# 10_LPDDR_SDRAM2.net
KiCad netlist of a schematic drawn in Altium Designer
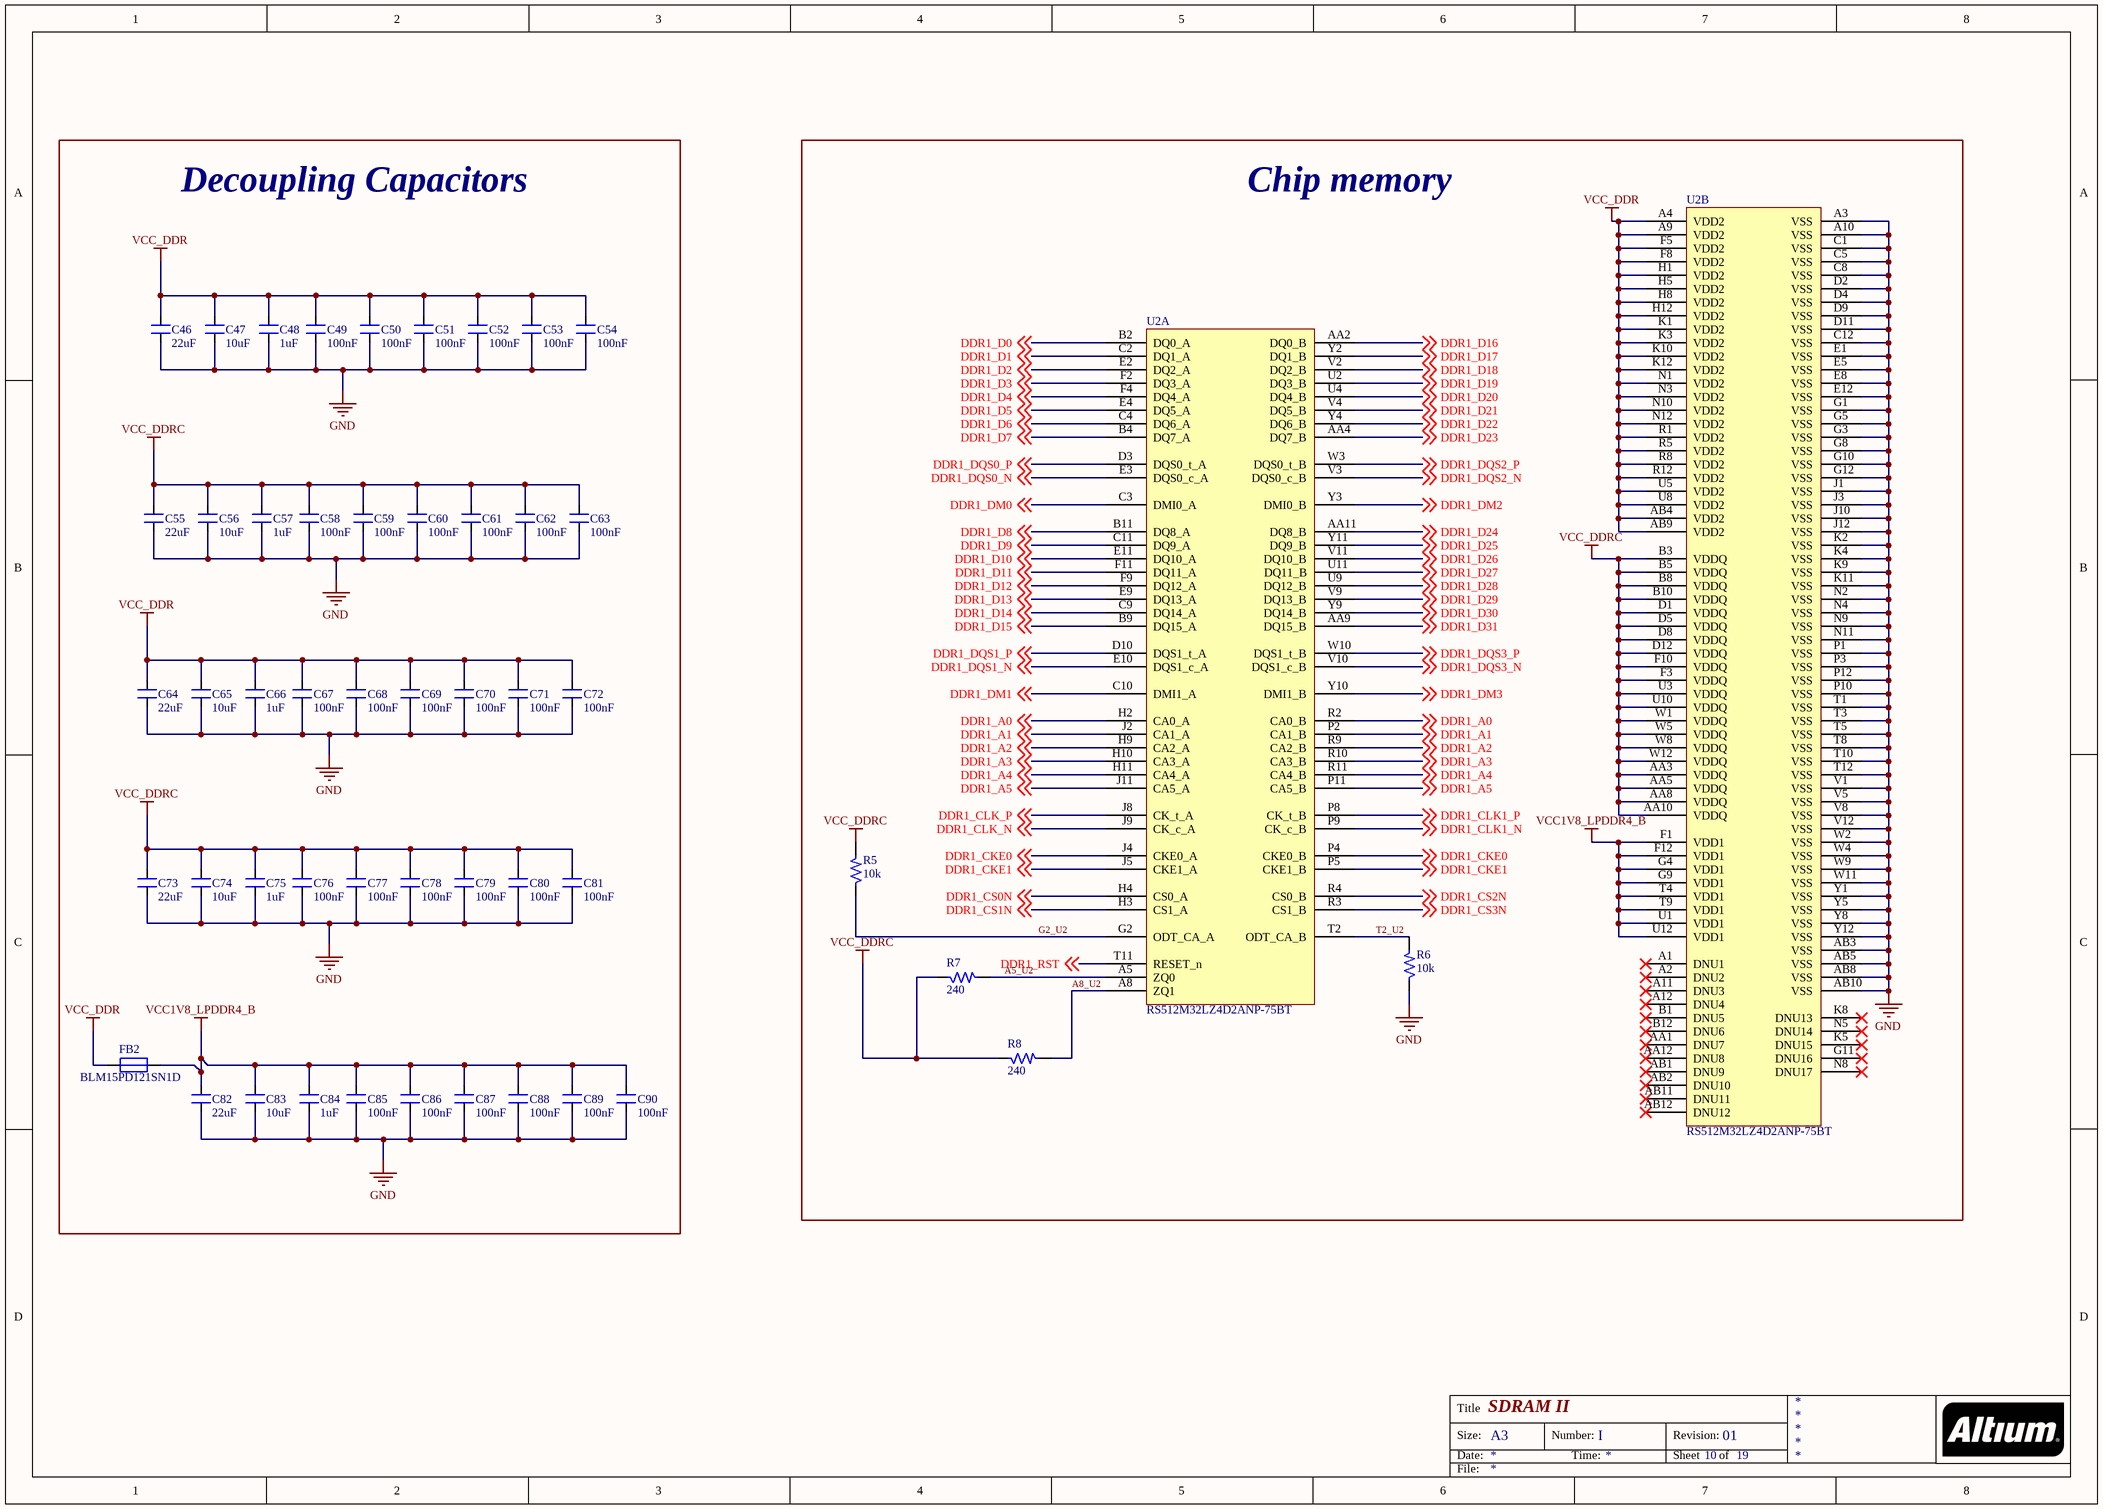
[diagram p0: [10] LPDDR_SDRAM2.SchDoc]

(export (version "E")
  (design (tool "Eeschema 10.0.6"))
  (components
    (comp (ref "C46")
      (value "22uF")
      (footprint "CAP_0402")
      (description "22µF ±20% 6.3V Ceramic Capacitor X5R 0402 (1005 Metric)")
      (fields
        (field (name "MANUFACTURER") "Murata Electronics")
        (field (name "MANUFACTURER PART NUMBER") "CL05A226MQ5N6J8")
      )
      (libsource (lib "EsteemPCB_SOM_Course_intlib") (part "CAP_22uF-6.3V-20%-0402"))
    )
    (comp (ref "C47")
      (value "10uF")
      (footprint "CAP_0402")
      (description "10µF ±20% 10V Ceramic Capacitor X5R 0402 (1005 Metric)")
      (fields
        (field (name "MANUFACTURER PART NUMBER") "CL05A106MP5NUNC")
        (field (name "MANUFACTURER") "Samsung Electro-Mechanics")
      )
      (libsource (lib "EsteemPCB_SOM_Course_intlib") (part "CAP_10uF-10V-20%-0402"))
    )
    (comp (ref "C48")
      (value "1uF")
      (footprint "CAP_0201")
      (description "1µF ±20% 16V Ceramic Capacitor X5R 0201 (0603 Metric)")
      (fields
        (field (name "MANUFACTURER") "Samsung Electro-Mechanics")
        (field (name "MANUFACTURER PART NUMBER") "CL03A105MO3NRNH")
      )
      (libsource (lib "EsteemPCB_SOM_Course_intlib") (part "CAP_1uF-16V-10%-0201"))
    )
    (comp (ref "C49")
      (value "100nF")
      (footprint "CAP_0201")
      (description "0.1µF ±10% 25V Ceramic Capacitor X5R 0201 (0603 Metric)")
      (fields
        (field (name "MANUFACTURER") "TDK Corporation")
        (field (name "MANUFACTURER PART NUMBER") "C0603X5R1E104K030BB")
      )
      (libsource (lib "EsteemPCB_SOM_Course_intlib") (part "CAP_100nF-25V-10%-0201"))
    )
    (comp (ref "C50")
      (value "100nF")
      (footprint "CAP_0201")
      (description "0.1µF ±10% 25V Ceramic Capacitor X5R 0201 (0603 Metric)")
      (fields
        (field (name "MANUFACTURER") "TDK Corporation")
        (field (name "MANUFACTURER PART NUMBER") "C0603X5R1E104K030BB")
      )
      (libsource (lib "EsteemPCB_SOM_Course_intlib") (part "CAP_100nF-25V-10%-0201"))
    )
    (comp (ref "C51")
      (value "100nF")
      (footprint "CAP_0201")
      (description "0.1µF ±10% 25V Ceramic Capacitor X5R 0201 (0603 Metric)")
      (fields
        (field (name "MANUFACTURER") "TDK Corporation")
        (field (name "MANUFACTURER PART NUMBER") "C0603X5R1E104K030BB")
      )
      (libsource (lib "EsteemPCB_SOM_Course_intlib") (part "CAP_100nF-25V-10%-0201"))
    )
    (comp (ref "C52")
      (value "100nF")
      (footprint "CAP_0201")
      (description "0.1µF ±10% 25V Ceramic Capacitor X5R 0201 (0603 Metric)")
      (fields
        (field (name "MANUFACTURER") "TDK Corporation")
        (field (name "MANUFACTURER PART NUMBER") "C0603X5R1E104K030BB")
      )
      (libsource (lib "EsteemPCB_SOM_Course_intlib") (part "CAP_100nF-25V-10%-0201"))
    )
    (comp (ref "C53")
      (value "100nF")
      (footprint "CAP_0201")
      (description "0.1µF ±10% 25V Ceramic Capacitor X5R 0201 (0603 Metric)")
      (fields
        (field (name "MANUFACTURER") "TDK Corporation")
        (field (name "MANUFACTURER PART NUMBER") "C0603X5R1E104K030BB")
      )
      (libsource (lib "EsteemPCB_SOM_Course_intlib") (part "CAP_100nF-25V-10%-0201"))
    )
    (comp (ref "C54")
      (value "100nF")
      (footprint "CAP_0201")
      (description "0.1µF ±10% 25V Ceramic Capacitor X5R 0201 (0603 Metric)")
      (fields
        (field (name "MANUFACTURER") "TDK Corporation")
        (field (name "MANUFACTURER PART NUMBER") "C0603X5R1E104K030BB")
      )
      (libsource (lib "EsteemPCB_SOM_Course_intlib") (part "CAP_100nF-25V-10%-0201"))
    )
    (comp (ref "C55")
      (value "22uF")
      (footprint "CAP_0402")
      (description "22µF ±20% 6.3V Ceramic Capacitor X5R 0402 (1005 Metric)")
      (fields
        (field (name "MANUFACTURER") "Murata Electronics")
        (field (name "MANUFACTURER PART NUMBER") "CL05A226MQ5N6J8")
      )
      (libsource (lib "EsteemPCB_SOM_Course_intlib") (part "CAP_22uF-6.3V-20%-0402"))
    )
    (comp (ref "C56")
      (value "10uF")
      (footprint "CAP_0402")
      (description "10µF ±20% 10V Ceramic Capacitor X5R 0402 (1005 Metric)")
      (fields
        (field (name "MANUFACTURER PART NUMBER") "CL05A106MP5NUNC")
        (field (name "MANUFACTURER") "Samsung Electro-Mechanics")
      )
      (libsource (lib "EsteemPCB_SOM_Course_intlib") (part "CAP_10uF-10V-20%-0402"))
    )
    (comp (ref "C57")
      (value "1uF")
      (footprint "CAP_0201")
      (description "1µF ±20% 16V Ceramic Capacitor X5R 0201 (0603 Metric)")
      (fields
        (field (name "MANUFACTURER") "Samsung Electro-Mechanics")
        (field (name "MANUFACTURER PART NUMBER") "CL03A105MO3NRNH")
      )
      (libsource (lib "EsteemPCB_SOM_Course_intlib") (part "CAP_1uF-16V-10%-0201"))
    )
    (comp (ref "C58")
      (value "100nF")
      (footprint "CAP_0201")
      (description "0.1µF ±10% 25V Ceramic Capacitor X5R 0201 (0603 Metric)")
      (fields
        (field (name "MANUFACTURER") "TDK Corporation")
        (field (name "MANUFACTURER PART NUMBER") "C0603X5R1E104K030BB")
      )
      (libsource (lib "EsteemPCB_SOM_Course_intlib") (part "CAP_100nF-25V-10%-0201"))
    )
    (comp (ref "C59")
      (value "100nF")
      (footprint "CAP_0201")
      (description "0.1µF ±10% 25V Ceramic Capacitor X5R 0201 (0603 Metric)")
      (fields
        (field (name "MANUFACTURER") "TDK Corporation")
        (field (name "MANUFACTURER PART NUMBER") "C0603X5R1E104K030BB")
      )
      (libsource (lib "EsteemPCB_SOM_Course_intlib") (part "CAP_100nF-25V-10%-0201"))
    )
    (comp (ref "C60")
      (value "100nF")
      (footprint "CAP_0201")
      (description "0.1µF ±10% 25V Ceramic Capacitor X5R 0201 (0603 Metric)")
      (fields
        (field (name "MANUFACTURER") "TDK Corporation")
        (field (name "MANUFACTURER PART NUMBER") "C0603X5R1E104K030BB")
      )
      (libsource (lib "EsteemPCB_SOM_Course_intlib") (part "CAP_100nF-25V-10%-0201"))
    )
    (comp (ref "C61")
      (value "100nF")
      (footprint "CAP_0201")
      (description "0.1µF ±10% 25V Ceramic Capacitor X5R 0201 (0603 Metric)")
      (fields
        (field (name "MANUFACTURER") "TDK Corporation")
        (field (name "MANUFACTURER PART NUMBER") "C0603X5R1E104K030BB")
      )
      (libsource (lib "EsteemPCB_SOM_Course_intlib") (part "CAP_100nF-25V-10%-0201"))
    )
    (comp (ref "C62")
      (value "100nF")
      (footprint "CAP_0201")
      (description "0.1µF ±10% 25V Ceramic Capacitor X5R 0201 (0603 Metric)")
      (fields
        (field (name "MANUFACTURER") "TDK Corporation")
        (field (name "MANUFACTURER PART NUMBER") "C0603X5R1E104K030BB")
      )
      (libsource (lib "EsteemPCB_SOM_Course_intlib") (part "CAP_100nF-25V-10%-0201"))
    )
    (comp (ref "C63")
      (value "100nF")
      (footprint "CAP_0201")
      (description "0.1µF ±10% 25V Ceramic Capacitor X5R 0201 (0603 Metric)")
      (fields
        (field (name "MANUFACTURER") "TDK Corporation")
        (field (name "MANUFACTURER PART NUMBER") "C0603X5R1E104K030BB")
      )
      (libsource (lib "EsteemPCB_SOM_Course_intlib") (part "CAP_100nF-25V-10%-0201"))
    )
    (comp (ref "C64")
      (value "22uF")
      (footprint "CAP_0402")
      (description "22µF ±20% 6.3V Ceramic Capacitor X5R 0402 (1005 Metric)")
      (fields
        (field (name "MANUFACTURER") "Murata Electronics")
        (field (name "MANUFACTURER PART NUMBER") "CL05A226MQ5N6J8")
      )
      (libsource (lib "EsteemPCB_SOM_Course_intlib") (part "CAP_22uF-6.3V-20%-0402"))
    )
    (comp (ref "C65")
      (value "10uF")
      (footprint "CAP_0402")
      (description "10µF ±20% 10V Ceramic Capacitor X5R 0402 (1005 Metric)")
      (fields
        (field (name "MANUFACTURER PART NUMBER") "CL05A106MP5NUNC")
        (field (name "MANUFACTURER") "Samsung Electro-Mechanics")
      )
      (libsource (lib "EsteemPCB_SOM_Course_intlib") (part "CAP_10uF-10V-20%-0402"))
    )
    (comp (ref "C66")
      (value "1uF")
      (footprint "CAP_0201")
      (description "1µF ±20% 16V Ceramic Capacitor X5R 0201 (0603 Metric)")
      (fields
        (field (name "MANUFACTURER") "Samsung Electro-Mechanics")
        (field (name "MANUFACTURER PART NUMBER") "CL03A105MO3NRNH")
      )
      (libsource (lib "EsteemPCB_SOM_Course_intlib") (part "CAP_1uF-16V-10%-0201"))
    )
    (comp (ref "C67")
      (value "100nF")
      (footprint "CAP_0201")
      (description "0.1µF ±10% 25V Ceramic Capacitor X5R 0201 (0603 Metric)")
      (fields
        (field (name "MANUFACTURER") "TDK Corporation")
        (field (name "MANUFACTURER PART NUMBER") "C0603X5R1E104K030BB")
      )
      (libsource (lib "EsteemPCB_SOM_Course_intlib") (part "CAP_100nF-25V-10%-0201"))
    )
    (comp (ref "C68")
      (value "100nF")
      (footprint "CAP_0201")
      (description "0.1µF ±10% 25V Ceramic Capacitor X5R 0201 (0603 Metric)")
      (fields
        (field (name "MANUFACTURER") "TDK Corporation")
        (field (name "MANUFACTURER PART NUMBER") "C0603X5R1E104K030BB")
      )
      (libsource (lib "EsteemPCB_SOM_Course_intlib") (part "CAP_100nF-25V-10%-0201"))
    )
    (comp (ref "C69")
      (value "100nF")
      (footprint "CAP_0201")
      (description "0.1µF ±10% 25V Ceramic Capacitor X5R 0201 (0603 Metric)")
      (fields
        (field (name "MANUFACTURER") "TDK Corporation")
        (field (name "MANUFACTURER PART NUMBER") "C0603X5R1E104K030BB")
      )
      (libsource (lib "EsteemPCB_SOM_Course_intlib") (part "CAP_100nF-25V-10%-0201"))
    )
    (comp (ref "C70")
      (value "100nF")
      (footprint "CAP_0201")
      (description "0.1µF ±10% 25V Ceramic Capacitor X5R 0201 (0603 Metric)")
      (fields
        (field (name "MANUFACTURER") "TDK Corporation")
        (field (name "MANUFACTURER PART NUMBER") "C0603X5R1E104K030BB")
      )
      (libsource (lib "EsteemPCB_SOM_Course_intlib") (part "CAP_100nF-25V-10%-0201"))
    )
    (comp (ref "C71")
      (value "100nF")
      (footprint "CAP_0201")
      (description "0.1µF ±10% 25V Ceramic Capacitor X5R 0201 (0603 Metric)")
      (fields
        (field (name "MANUFACTURER") "TDK Corporation")
        (field (name "MANUFACTURER PART NUMBER") "C0603X5R1E104K030BB")
      )
      (libsource (lib "EsteemPCB_SOM_Course_intlib") (part "CAP_100nF-25V-10%-0201"))
    )
    (comp (ref "C72")
      (value "100nF")
      (footprint "CAP_0201")
      (description "0.1µF ±10% 25V Ceramic Capacitor X5R 0201 (0603 Metric)")
      (fields
        (field (name "MANUFACTURER") "TDK Corporation")
        (field (name "MANUFACTURER PART NUMBER") "C0603X5R1E104K030BB")
      )
      (libsource (lib "EsteemPCB_SOM_Course_intlib") (part "CAP_100nF-25V-10%-0201"))
    )
    (comp (ref "C73")
      (value "22uF")
      (footprint "CAP_0402")
      (description "22µF ±20% 6.3V Ceramic Capacitor X5R 0402 (1005 Metric)")
      (fields
        (field (name "MANUFACTURER") "Murata Electronics")
        (field (name "MANUFACTURER PART NUMBER") "CL05A226MQ5N6J8")
      )
      (libsource (lib "EsteemPCB_SOM_Course_intlib") (part "CAP_22uF-6.3V-20%-0402"))
    )
    (comp (ref "C74")
      (value "10uF")
      (footprint "CAP_0402")
      (description "10µF ±20% 10V Ceramic Capacitor X5R 0402 (1005 Metric)")
      (fields
        (field (name "MANUFACTURER PART NUMBER") "CL05A106MP5NUNC")
        (field (name "MANUFACTURER") "Samsung Electro-Mechanics")
      )
      (libsource (lib "EsteemPCB_SOM_Course_intlib") (part "CAP_10uF-10V-20%-0402"))
    )
    (comp (ref "C75")
      (value "1uF")
      (footprint "CAP_0201")
      (description "1µF ±20% 16V Ceramic Capacitor X5R 0201 (0603 Metric)")
      (fields
        (field (name "MANUFACTURER") "Samsung Electro-Mechanics")
        (field (name "MANUFACTURER PART NUMBER") "CL03A105MO3NRNH")
      )
      (libsource (lib "EsteemPCB_SOM_Course_intlib") (part "CAP_1uF-16V-10%-0201"))
    )
    (comp (ref "C76")
      (value "100nF")
      (footprint "CAP_0201")
      (description "0.1µF ±10% 25V Ceramic Capacitor X5R 0201 (0603 Metric)")
      (fields
        (field (name "MANUFACTURER") "TDK Corporation")
        (field (name "MANUFACTURER PART NUMBER") "C0603X5R1E104K030BB")
      )
      (libsource (lib "EsteemPCB_SOM_Course_intlib") (part "CAP_100nF-25V-10%-0201"))
    )
    (comp (ref "C77")
      (value "100nF")
      (footprint "CAP_0201")
      (description "0.1µF ±10% 25V Ceramic Capacitor X5R 0201 (0603 Metric)")
      (fields
        (field (name "MANUFACTURER") "TDK Corporation")
        (field (name "MANUFACTURER PART NUMBER") "C0603X5R1E104K030BB")
      )
      (libsource (lib "EsteemPCB_SOM_Course_intlib") (part "CAP_100nF-25V-10%-0201"))
    )
    (comp (ref "C78")
      (value "100nF")
      (footprint "CAP_0201")
      (description "0.1µF ±10% 25V Ceramic Capacitor X5R 0201 (0603 Metric)")
      (fields
        (field (name "MANUFACTURER") "TDK Corporation")
        (field (name "MANUFACTURER PART NUMBER") "C0603X5R1E104K030BB")
      )
      (libsource (lib "EsteemPCB_SOM_Course_intlib") (part "CAP_100nF-25V-10%-0201"))
    )
    (comp (ref "C79")
      (value "100nF")
      (footprint "CAP_0201")
      (description "0.1µF ±10% 25V Ceramic Capacitor X5R 0201 (0603 Metric)")
      (fields
        (field (name "MANUFACTURER") "TDK Corporation")
        (field (name "MANUFACTURER PART NUMBER") "C0603X5R1E104K030BB")
      )
      (libsource (lib "EsteemPCB_SOM_Course_intlib") (part "CAP_100nF-25V-10%-0201"))
    )
    (comp (ref "C80")
      (value "100nF")
      (footprint "CAP_0201")
      (description "0.1µF ±10% 25V Ceramic Capacitor X5R 0201 (0603 Metric)")
      (fields
        (field (name "MANUFACTURER") "TDK Corporation")
        (field (name "MANUFACTURER PART NUMBER") "C0603X5R1E104K030BB")
      )
      (libsource (lib "EsteemPCB_SOM_Course_intlib") (part "CAP_100nF-25V-10%-0201"))
    )
    (comp (ref "C81")
      (value "100nF")
      (footprint "CAP_0201")
      (description "0.1µF ±10% 25V Ceramic Capacitor X5R 0201 (0603 Metric)")
      (fields
        (field (name "MANUFACTURER") "TDK Corporation")
        (field (name "MANUFACTURER PART NUMBER") "C0603X5R1E104K030BB")
      )
      (libsource (lib "EsteemPCB_SOM_Course_intlib") (part "CAP_100nF-25V-10%-0201"))
    )
    (comp (ref "C82")
      (value "22uF")
      (footprint "CAP_0402")
      (description "22µF ±20% 6.3V Ceramic Capacitor X5R 0402 (1005 Metric)")
      (fields
        (field (name "MANUFACTURER") "Murata Electronics")
        (field (name "MANUFACTURER PART NUMBER") "CL05A226MQ5N6J8")
      )
      (libsource (lib "EsteemPCB_SOM_Course_intlib") (part "CAP_22uF-6.3V-20%-0402"))
    )
    (comp (ref "C83")
      (value "10uF")
      (footprint "CAP_0402")
      (description "10µF ±20% 10V Ceramic Capacitor X5R 0402 (1005 Metric)")
      (fields
        (field (name "MANUFACTURER PART NUMBER") "CL05A106MP5NUNC")
        (field (name "MANUFACTURER") "Samsung Electro-Mechanics")
      )
      (libsource (lib "EsteemPCB_SOM_Course_intlib") (part "CAP_10uF-10V-20%-0402"))
    )
    (comp (ref "C84")
      (value "1uF")
      (footprint "CAP_0201")
      (description "1µF ±20% 16V Ceramic Capacitor X5R 0201 (0603 Metric)")
      (fields
        (field (name "MANUFACTURER") "Samsung Electro-Mechanics")
        (field (name "MANUFACTURER PART NUMBER") "CL03A105MO3NRNH")
      )
      (libsource (lib "EsteemPCB_SOM_Course_intlib") (part "CAP_1uF-16V-10%-0201"))
    )
    (comp (ref "C85")
      (value "100nF")
      (footprint "CAP_0201")
      (description "0.1µF ±10% 25V Ceramic Capacitor X5R 0201 (0603 Metric)")
      (fields
        (field (name "MANUFACTURER") "TDK Corporation")
        (field (name "MANUFACTURER PART NUMBER") "C0603X5R1E104K030BB")
      )
      (libsource (lib "EsteemPCB_SOM_Course_intlib") (part "CAP_100nF-25V-10%-0201"))
    )
    (comp (ref "C86")
      (value "100nF")
      (footprint "CAP_0201")
      (description "0.1µF ±10% 25V Ceramic Capacitor X5R 0201 (0603 Metric)")
      (fields
        (field (name "MANUFACTURER") "TDK Corporation")
        (field (name "MANUFACTURER PART NUMBER") "C0603X5R1E104K030BB")
      )
      (libsource (lib "EsteemPCB_SOM_Course_intlib") (part "CAP_100nF-25V-10%-0201"))
    )
    (comp (ref "C87")
      (value "100nF")
      (footprint "CAP_0201")
      (description "0.1µF ±10% 25V Ceramic Capacitor X5R 0201 (0603 Metric)")
      (fields
        (field (name "MANUFACTURER") "TDK Corporation")
        (field (name "MANUFACTURER PART NUMBER") "C0603X5R1E104K030BB")
      )
      (libsource (lib "EsteemPCB_SOM_Course_intlib") (part "CAP_100nF-25V-10%-0201"))
    )
    (comp (ref "C88")
      (value "100nF")
      (footprint "CAP_0201")
      (description "0.1µF ±10% 25V Ceramic Capacitor X5R 0201 (0603 Metric)")
      (fields
        (field (name "MANUFACTURER") "TDK Corporation")
        (field (name "MANUFACTURER PART NUMBER") "C0603X5R1E104K030BB")
      )
      (libsource (lib "EsteemPCB_SOM_Course_intlib") (part "CAP_100nF-25V-10%-0201"))
    )
    (comp (ref "C89")
      (value "100nF")
      (footprint "CAP_0201")
      (description "0.1µF ±10% 25V Ceramic Capacitor X5R 0201 (0603 Metric)")
      (fields
        (field (name "MANUFACTURER") "TDK Corporation")
        (field (name "MANUFACTURER PART NUMBER") "C0603X5R1E104K030BB")
      )
      (libsource (lib "EsteemPCB_SOM_Course_intlib") (part "CAP_100nF-25V-10%-0201"))
    )
    (comp (ref "C90")
      (value "100nF")
      (footprint "CAP_0201")
      (description "0.1µF ±10% 25V Ceramic Capacitor X5R 0201 (0603 Metric)")
      (fields
        (field (name "MANUFACTURER") "TDK Corporation")
        (field (name "MANUFACTURER PART NUMBER") "C0603X5R1E104K030BB")
      )
      (libsource (lib "EsteemPCB_SOM_Course_intlib") (part "CAP_100nF-25V-10%-0201"))
    )
    (comp (ref "FB2")
      (value "BLM15PD121SN1D")
      (footprint "RES_0402")
      (description "120 Ohms @ 100MHz 1 Power Line Ferrite Bead 0402 (1005 Metric) 1.3A 90mOhm")
      (fields (field (name "MANUFACTURER") "Murata Electronics"))
      (libsource (lib "EsteemPCB_SOM_Course_intlib") (part "FB_120R-1.3A-100Mhz-0402"))
    )
    (comp (ref "R5")
      (value "10k")
      (footprint "RES_0201")
      (description "0 Ohms Jumper 0.05W, 1/20W Chip Resistor 0201 (0603 Metric) Automotive AEC-Q200 Thick Film")
      (fields
        (field (name "MANUFACTURER") "Bourns Inc.")
        (field (name "MANUFACTURER PART NUMBER") "CR0201AJ/-000GLF")
      )
      (libsource (lib "EsteemPCB_SOM_Course_intlib") (part "RES_0R-0.05W-1%-0201"))
    )
    (comp (ref "R6")
      (value "10k")
      (footprint "RES_0201")
      (description "0 Ohms Jumper 0.05W, 1/20W Chip Resistor 0201 (0603 Metric) Automotive AEC-Q200 Thick Film")
      (fields
        (field (name "MANUFACTURER") "Bourns Inc.")
        (field (name "MANUFACTURER PART NUMBER") "CR0201AJ/-000GLF")
      )
      (libsource (lib "EsteemPCB_SOM_Course_intlib") (part "RES_0R-0.05W-1%-0201"))
    )
    (comp (ref "R7")
      (value "240")
      (footprint "RES_0201")
      (description "0 Ohms Jumper 0.05W, 1/20W Chip Resistor 0201 (0603 Metric) Automotive AEC-Q200 Thick Film")
      (fields
        (field (name "MANUFACTURER") "Bourns Inc.")
        (field (name "MANUFACTURER PART NUMBER") "CR0201AJ/-000GLF")
      )
      (libsource (lib "EsteemPCB_SOM_Course_intlib") (part "RES_0R-0.05W-1%-0201"))
    )
    (comp (ref "R8")
      (value "240")
      (footprint "RES_0201")
      (description "0 Ohms Jumper 0.05W, 1/20W Chip Resistor 0201 (0603 Metric) Automotive AEC-Q200 Thick Film")
      (fields
        (field (name "MANUFACTURER") "Bourns Inc.")
        (field (name "MANUFACTURER PART NUMBER") "CR0201AJ/-000GLF")
      )
      (libsource (lib "EsteemPCB_SOM_Course_intlib") (part "RES_0R-0.05W-1%-0201"))
    )
    (comp (ref "U2")
      (value "RS512M32LZ4D2ANP-75BT")
      (footprint "FBGA200_SMD")
      (fields (field (name "MANUFACTURER") "RAYSON"))
      (libsource (lib "RK3399 _Module_Schlib") (part "IC_RS512M32LZ4D2ANP-75BT"))
    )
  )
  (nets
    (net (code "1") (name "/A5_U2") (class "Default")
      (node (ref "R7") (pin "2") (pinfunction "2_2") (pintype "passive"))
      (node (ref "U2") (pin "A5") (pinfunction "ZQ0_A5") (pintype "passive"))
    )
    (net (code "2") (name "/A8_U2") (class "Default")
      (node (ref "R8") (pin "2") (pinfunction "2_2") (pintype "passive"))
      (node (ref "U2") (pin "A8") (pinfunction "ZQ1_A8") (pintype "passive"))
    )
    (net (code "3") (name "/G2_U2") (class "Default")
      (node (ref "R5") (pin "1") (pinfunction "1_1") (pintype "passive"))
      (node (ref "U2") (pin "G2") (pinfunction "ODT_CA_A_G2") (pintype "passive"))
    )
    (net (code "4") (name "/T2_U2") (class "Default")
      (node (ref "R6") (pin "2") (pinfunction "2_2") (pintype "passive"))
      (node (ref "U2") (pin "T2") (pinfunction "ODT_CA_B_T2") (pintype "passive"))
    )
    (net (code "5") (name "DDR1_A0") (class "Default")
      (node (ref "U2") (pin "H2") (pinfunction "CA0_A_H2") (pintype "passive"))
      (node (ref "U2") (pin "R2") (pinfunction "CA0_B_R2") (pintype "passive"))
    )
    (net (code "6") (name "DDR1_A1") (class "Default")
      (node (ref "U2") (pin "J2") (pinfunction "CA1_A_J2") (pintype "passive"))
      (node (ref "U2") (pin "P2") (pinfunction "CA1_B_P2") (pintype "passive"))
    )
    (net (code "7") (name "DDR1_A2") (class "Default")
      (node (ref "U2") (pin "H9") (pinfunction "CA2_A_H9") (pintype "passive"))
      (node (ref "U2") (pin "R9") (pinfunction "CA2_B_R9") (pintype "passive"))
    )
    (net (code "8") (name "DDR1_A3") (class "Default")
      (node (ref "U2") (pin "H10") (pinfunction "CA3_A_H10") (pintype "passive"))
      (node (ref "U2") (pin "R10") (pinfunction "CA3_B_R10") (pintype "passive"))
    )
    (net (code "9") (name "DDR1_A4") (class "Default")
      (node (ref "U2") (pin "H11") (pinfunction "CA4_A_H11") (pintype "passive"))
      (node (ref "U2") (pin "R11") (pinfunction "CA4_B_R11") (pintype "passive"))
    )
    (net (code "10") (name "DDR1_A5") (class "Default")
      (node (ref "U2") (pin "J11") (pinfunction "CA5_A_J11") (pintype "passive"))
      (node (ref "U2") (pin "P11") (pinfunction "CA5_B_P11") (pintype "passive"))
    )
    (net (code "11") (name "DDR1_CKE0") (class "Default")
      (node (ref "U2") (pin "J4") (pinfunction "CKE0_A_J4") (pintype "passive"))
      (node (ref "U2") (pin "P4") (pinfunction "CKE0_B_P4") (pintype "passive"))
    )
    (net (code "12") (name "DDR1_CKE1") (class "Default")
      (node (ref "U2") (pin "J5") (pinfunction "CKE1_A_J5") (pintype "passive"))
      (node (ref "U2") (pin "P5") (pinfunction "CKE1_B_P5") (pintype "passive"))
    )
    (net (code "13") (name "DDR1_CLK1_N") (class "Default")
      (node (ref "U2") (pin "P9") (pinfunction "CK_c_B_P9") (pintype "passive"))
    )
    (net (code "14") (name "DDR1_CLK1_P") (class "Default")
      (node (ref "U2") (pin "P8") (pinfunction "CK_t_B_P8") (pintype "passive"))
    )
    (net (code "15") (name "DDR1_CLK_N") (class "Default")
      (node (ref "U2") (pin "J9") (pinfunction "CK_c_A_J9") (pintype "passive"))
    )
    (net (code "16") (name "DDR1_CLK_P") (class "Default")
      (node (ref "U2") (pin "J8") (pinfunction "CK_t_A_J8") (pintype "passive"))
    )
    (net (code "17") (name "DDR1_CS0N") (class "Default")
      (node (ref "U2") (pin "H4") (pinfunction "CS0_A_H4") (pintype "passive"))
    )
    (net (code "18") (name "DDR1_CS1N") (class "Default")
      (node (ref "U2") (pin "H3") (pinfunction "CS1_A_H3") (pintype "passive"))
    )
    (net (code "19") (name "DDR1_CS2N") (class "Default")
      (node (ref "U2") (pin "R4") (pinfunction "CS0_B_R4") (pintype "passive"))
    )
    (net (code "20") (name "DDR1_CS3N") (class "Default")
      (node (ref "U2") (pin "R3") (pinfunction "CS1_B_R3") (pintype "passive"))
    )
    (net (code "21") (name "DDR1_D0") (class "Default")
      (node (ref "U2") (pin "B2") (pinfunction "DQ0_A_B2") (pintype "passive"))
    )
    (net (code "22") (name "DDR1_D1") (class "Default")
      (node (ref "U2") (pin "C2") (pinfunction "DQ1_A_C2") (pintype "passive"))
    )
    (net (code "23") (name "DDR1_D2") (class "Default")
      (node (ref "U2") (pin "E2") (pinfunction "DQ2_A_E2") (pintype "passive"))
    )
    (net (code "24") (name "DDR1_D3") (class "Default")
      (node (ref "U2") (pin "F2") (pinfunction "DQ3_A_F2") (pintype "passive"))
    )
    (net (code "25") (name "DDR1_D4") (class "Default")
      (node (ref "U2") (pin "F4") (pinfunction "DQ4_A_F4") (pintype "passive"))
    )
    (net (code "26") (name "DDR1_D5") (class "Default")
      (node (ref "U2") (pin "E4") (pinfunction "DQ5_A_E4") (pintype "passive"))
    )
    (net (code "27") (name "DDR1_D6") (class "Default")
      (node (ref "U2") (pin "C4") (pinfunction "DQ6_A_C4") (pintype "passive"))
    )
    (net (code "28") (name "DDR1_D7") (class "Default")
      (node (ref "U2") (pin "B4") (pinfunction "DQ7_A_B4") (pintype "passive"))
    )
    (net (code "29") (name "DDR1_D8") (class "Default")
      (node (ref "U2") (pin "B11") (pinfunction "DQ8_A_B11") (pintype "passive"))
    )
    (net (code "30") (name "DDR1_D9") (class "Default")
      (node (ref "U2") (pin "C11") (pinfunction "DQ9_A_C11") (pintype "passive"))
    )
    (net (code "31") (name "DDR1_D10") (class "Default")
      (node (ref "U2") (pin "E11") (pinfunction "DQ10_A_E11") (pintype "passive"))
    )
    (net (code "32") (name "DDR1_D11") (class "Default")
      (node (ref "U2") (pin "F11") (pinfunction "DQ11_A_F11") (pintype "passive"))
    )
    (net (code "33") (name "DDR1_D12") (class "Default")
      (node (ref "U2") (pin "F9") (pinfunction "DQ12_A_F9") (pintype "passive"))
    )
    (net (code "34") (name "DDR1_D13") (class "Default")
      (node (ref "U2") (pin "E9") (pinfunction "DQ13_A_E9") (pintype "passive"))
    )
    (net (code "35") (name "DDR1_D14") (class "Default")
      (node (ref "U2") (pin "C9") (pinfunction "DQ14_A_C9") (pintype "passive"))
    )
    (net (code "36") (name "DDR1_D15") (class "Default")
      (node (ref "U2") (pin "B9") (pinfunction "DQ15_A_B9") (pintype "passive"))
    )
    (net (code "37") (name "DDR1_D16") (class "Default")
      (node (ref "U2") (pin "AA2") (pinfunction "DQ0_B_AA2") (pintype "passive"))
    )
    (net (code "38") (name "DDR1_D17") (class "Default")
      (node (ref "U2") (pin "Y2") (pinfunction "DQ1_B_Y2") (pintype "passive"))
    )
    (net (code "39") (name "DDR1_D18") (class "Default")
      (node (ref "U2") (pin "V2") (pinfunction "DQ2_B_V2") (pintype "passive"))
    )
    (net (code "40") (name "DDR1_D19") (class "Default")
      (node (ref "U2") (pin "U2") (pinfunction "DQ3_B_U2") (pintype "passive"))
    )
    (net (code "41") (name "DDR1_D20") (class "Default")
      (node (ref "U2") (pin "U4") (pinfunction "DQ4_B_U4") (pintype "passive"))
    )
    (net (code "42") (name "DDR1_D21") (class "Default")
      (node (ref "U2") (pin "V4") (pinfunction "DQ5_B_V4") (pintype "passive"))
    )
    (net (code "43") (name "DDR1_D22") (class "Default")
      (node (ref "U2") (pin "Y4") (pinfunction "DQ6_B_Y4") (pintype "passive"))
    )
    (net (code "44") (name "DDR1_D23") (class "Default")
      (node (ref "U2") (pin "AA4") (pinfunction "DQ7_B_AA4") (pintype "passive"))
    )
    (net (code "45") (name "DDR1_D24") (class "Default")
      (node (ref "U2") (pin "AA11") (pinfunction "DQ8_B_AA11") (pintype "passive"))
    )
    (net (code "46") (name "DDR1_D25") (class "Default")
      (node (ref "U2") (pin "Y11") (pinfunction "DQ9_B_Y11") (pintype "passive"))
    )
    (net (code "47") (name "DDR1_D26") (class "Default")
      (node (ref "U2") (pin "V11") (pinfunction "DQ10_B_V11") (pintype "passive"))
    )
    (net (code "48") (name "DDR1_D27") (class "Default")
      (node (ref "U2") (pin "U11") (pinfunction "DQ11_B_U11") (pintype "passive"))
    )
    (net (code "49") (name "DDR1_D28") (class "Default")
      (node (ref "U2") (pin "U9") (pinfunction "DQ12_B_U9") (pintype "passive"))
    )
    (net (code "50") (name "DDR1_D29") (class "Default")
      (node (ref "U2") (pin "V9") (pinfunction "DQ13_B_V9") (pintype "passive"))
    )
    (net (code "51") (name "DDR1_D30") (class "Default")
      (node (ref "U2") (pin "Y9") (pinfunction "DQ14_B_Y9") (pintype "passive"))
    )
    (net (code "52") (name "DDR1_D31") (class "Default")
      (node (ref "U2") (pin "AA9") (pinfunction "DQ15_B_AA9") (pintype "passive"))
    )
    (net (code "53") (name "DDR1_DM0") (class "Default")
      (node (ref "U2") (pin "C3") (pinfunction "DMI0_A_C3") (pintype "passive"))
    )
    (net (code "54") (name "DDR1_DM1") (class "Default")
      (node (ref "U2") (pin "C10") (pinfunction "DMI1_A_C10") (pintype "passive"))
    )
    (net (code "55") (name "DDR1_DM2") (class "Default")
      (node (ref "U2") (pin "Y3") (pinfunction "DMI0_B_Y3") (pintype "passive"))
    )
    (net (code "56") (name "DDR1_DM3") (class "Default")
      (node (ref "U2") (pin "Y10") (pinfunction "DMI1_B_Y10") (pintype "passive"))
    )
    (net (code "57") (name "DDR1_DQS0_N") (class "Default")
      (node (ref "U2") (pin "E3") (pinfunction "DQS0_c_A_E3") (pintype "passive"))
    )
    (net (code "58") (name "DDR1_DQS0_P") (class "Default")
      (node (ref "U2") (pin "D3") (pinfunction "DQS0_t_A_D3") (pintype "passive"))
    )
    (net (code "59") (name "DDR1_DQS1_N") (class "Default")
      (node (ref "U2") (pin "E10") (pinfunction "DQS1_c_A_E10") (pintype "passive"))
    )
    (net (code "60") (name "DDR1_DQS1_P") (class "Default")
      (node (ref "U2") (pin "D10") (pinfunction "DQS1_t_A_D10") (pintype "passive"))
    )
    (net (code "61") (name "DDR1_DQS2_N") (class "Default")
      (node (ref "U2") (pin "V3") (pinfunction "DQS0_c_B_V3") (pintype "passive"))
    )
    (net (code "62") (name "DDR1_DQS2_P") (class "Default")
      (node (ref "U2") (pin "W3") (pinfunction "DQS0_t_B_W3") (pintype "passive"))
    )
    (net (code "63") (name "DDR1_DQS3_N") (class "Default")
      (node (ref "U2") (pin "V10") (pinfunction "DQS1_c_B_V10") (pintype "passive"))
    )
    (net (code "64") (name "DDR1_DQS3_P") (class "Default")
      (node (ref "U2") (pin "W10") (pinfunction "DQS1_t_B_W10") (pintype "passive"))
    )
    (net (code "65") (name "DDR1_RST") (class "Default")
      (node (ref "U2") (pin "T11") (pinfunction "RESET_n_T11") (pintype "passive"))
    )
    (net (code "66") (name "GND") (class "Default")
      (node (ref "C46") (pin "1") (pinfunction "1_1") (pintype "passive"))
      (node (ref "C47") (pin "1") (pinfunction "1_1") (pintype "passive"))
      (node (ref "C48") (pin "1") (pinfunction "1_1") (pintype "passive"))
      (node (ref "C49") (pin "1") (pinfunction "1_1") (pintype "passive"))
      (node (ref "C50") (pin "1") (pinfunction "1_1") (pintype "passive"))
      (node (ref "C51") (pin "1") (pinfunction "1_1") (pintype "passive"))
      (node (ref "C52") (pin "1") (pinfunction "1_1") (pintype "passive"))
      (node (ref "C53") (pin "1") (pinfunction "1_1") (pintype "passive"))
      (node (ref "C54") (pin "1") (pinfunction "1_1") (pintype "passive"))
      (node (ref "C55") (pin "1") (pinfunction "1_1") (pintype "passive"))
      (node (ref "C56") (pin "1") (pinfunction "1_1") (pintype "passive"))
      (node (ref "C57") (pin "1") (pinfunction "1_1") (pintype "passive"))
      (node (ref "C58") (pin "1") (pinfunction "1_1") (pintype "passive"))
      (node (ref "C59") (pin "1") (pinfunction "1_1") (pintype "passive"))
      (node (ref "C60") (pin "1") (pinfunction "1_1") (pintype "passive"))
      (node (ref "C61") (pin "1") (pinfunction "1_1") (pintype "passive"))
      (node (ref "C62") (pin "1") (pinfunction "1_1") (pintype "passive"))
      (node (ref "C63") (pin "1") (pinfunction "1_1") (pintype "passive"))
      (node (ref "C64") (pin "1") (pinfunction "1_1") (pintype "passive"))
      (node (ref "C65") (pin "1") (pinfunction "1_1") (pintype "passive"))
      (node (ref "C66") (pin "1") (pinfunction "1_1") (pintype "passive"))
      (node (ref "C67") (pin "1") (pinfunction "1_1") (pintype "passive"))
      (node (ref "C68") (pin "1") (pinfunction "1_1") (pintype "passive"))
      (node (ref "C69") (pin "1") (pinfunction "1_1") (pintype "passive"))
      (node (ref "C70") (pin "1") (pinfunction "1_1") (pintype "passive"))
      (node (ref "C71") (pin "1") (pinfunction "1_1") (pintype "passive"))
      (node (ref "C72") (pin "1") (pinfunction "1_1") (pintype "passive"))
      (node (ref "C73") (pin "1") (pinfunction "1_1") (pintype "passive"))
      (node (ref "C74") (pin "1") (pinfunction "1_1") (pintype "passive"))
      (node (ref "C75") (pin "1") (pinfunction "1_1") (pintype "passive"))
      (node (ref "C76") (pin "1") (pinfunction "1_1") (pintype "passive"))
      (node (ref "C77") (pin "1") (pinfunction "1_1") (pintype "passive"))
      (node (ref "C78") (pin "1") (pinfunction "1_1") (pintype "passive"))
      (node (ref "C79") (pin "1") (pinfunction "1_1") (pintype "passive"))
      (node (ref "C80") (pin "1") (pinfunction "1_1") (pintype "passive"))
      (node (ref "C81") (pin "1") (pinfunction "1_1") (pintype "passive"))
      (node (ref "C82") (pin "1") (pinfunction "1_1") (pintype "passive"))
      (node (ref "C83") (pin "1") (pinfunction "1_1") (pintype "passive"))
      (node (ref "C84") (pin "1") (pinfunction "1_1") (pintype "passive"))
      (node (ref "C85") (pin "1") (pinfunction "1_1") (pintype "passive"))
      (node (ref "C86") (pin "1") (pinfunction "1_1") (pintype "passive"))
      (node (ref "C87") (pin "1") (pinfunction "1_1") (pintype "passive"))
      (node (ref "C88") (pin "1") (pinfunction "1_1") (pintype "passive"))
      (node (ref "C89") (pin "1") (pinfunction "1_1") (pintype "passive"))
      (node (ref "C90") (pin "1") (pinfunction "1_1") (pintype "passive"))
      (node (ref "R6") (pin "1") (pinfunction "1_1") (pintype "passive"))
      (node (ref "U2") (pin "A10") (pinfunction "VSS_A10") (pintype "passive"))
      (node (ref "U2") (pin "A3") (pinfunction "VSS_A3") (pintype "passive"))
      (node (ref "U2") (pin "AB10") (pinfunction "VSS_AB10") (pintype "passive"))
      (node (ref "U2") (pin "AB3") (pinfunction "VSS_AB3") (pintype "passive"))
      (node (ref "U2") (pin "AB5") (pinfunction "VSS_AB5") (pintype "passive"))
      (node (ref "U2") (pin "AB8") (pinfunction "VSS_AB8") (pintype "passive"))
      (node (ref "U2") (pin "C1") (pinfunction "VSS_C1") (pintype "passive"))
      (node (ref "U2") (pin "C12") (pinfunction "VSS_C12") (pintype "passive"))
      (node (ref "U2") (pin "C5") (pinfunction "VSS_C5") (pintype "passive"))
      (node (ref "U2") (pin "C8") (pinfunction "VSS_C8") (pintype "passive"))
      (node (ref "U2") (pin "D11") (pinfunction "VSS_D11") (pintype "passive"))
      (node (ref "U2") (pin "D2") (pinfunction "VSS_D2") (pintype "passive"))
      (node (ref "U2") (pin "D4") (pinfunction "VSS_D4") (pintype "passive"))
      (node (ref "U2") (pin "D9") (pinfunction "VSS_D9") (pintype "passive"))
      (node (ref "U2") (pin "E1") (pinfunction "VSS_E1") (pintype "passive"))
      (node (ref "U2") (pin "E12") (pinfunction "VSS_E12") (pintype "passive"))
      (node (ref "U2") (pin "E5") (pinfunction "VSS_E5") (pintype "passive"))
      (node (ref "U2") (pin "E8") (pinfunction "VSS_E8") (pintype "passive"))
      (node (ref "U2") (pin "G1") (pinfunction "VSS_G1") (pintype "passive"))
      (node (ref "U2") (pin "G10") (pinfunction "VSS_G10") (pintype "passive"))
      (node (ref "U2") (pin "G12") (pinfunction "VSS_G12") (pintype "passive"))
      (node (ref "U2") (pin "G3") (pinfunction "VSS_G3") (pintype "passive"))
      (node (ref "U2") (pin "G5") (pinfunction "VSS_G5") (pintype "passive"))
      (node (ref "U2") (pin "G8") (pinfunction "VSS_G8") (pintype "passive"))
      (node (ref "U2") (pin "J1") (pinfunction "VSS_J1") (pintype "passive"))
      (node (ref "U2") (pin "J10") (pinfunction "VSS_J10") (pintype "passive"))
      (node (ref "U2") (pin "J12") (pinfunction "VSS_J12") (pintype "passive"))
      (node (ref "U2") (pin "J3") (pinfunction "VSS_J3") (pintype "passive"))
      (node (ref "U2") (pin "K11") (pinfunction "VSS_K11") (pintype "passive"))
      (node (ref "U2") (pin "K2") (pinfunction "VSS_K2") (pintype "passive"))
      (node (ref "U2") (pin "K4") (pinfunction "VSS_K4") (pintype "passive"))
      (node (ref "U2") (pin "K9") (pinfunction "VSS_K9") (pintype "passive"))
      (node (ref "U2") (pin "N11") (pinfunction "VSS_N11") (pintype "passive"))
      (node (ref "U2") (pin "N2") (pinfunction "VSS_N2") (pintype "passive"))
      (node (ref "U2") (pin "N4") (pinfunction "VSS_N4") (pintype "passive"))
      (node (ref "U2") (pin "N9") (pinfunction "VSS_N9") (pintype "passive"))
      (node (ref "U2") (pin "P1") (pinfunction "VSS_P1") (pintype "passive"))
      (node (ref "U2") (pin "P10") (pinfunction "VSS_P10") (pintype "passive"))
      (node (ref "U2") (pin "P12") (pinfunction "VSS_P12") (pintype "passive"))
      (node (ref "U2") (pin "P3") (pinfunction "VSS_P3") (pintype "passive"))
      (node (ref "U2") (pin "T1") (pinfunction "VSS_T1") (pintype "passive"))
      (node (ref "U2") (pin "T10") (pinfunction "VSS_T10") (pintype "passive"))
      (node (ref "U2") (pin "T12") (pinfunction "VSS_T12") (pintype "passive"))
      (node (ref "U2") (pin "T3") (pinfunction "VSS_T3") (pintype "passive"))
      (node (ref "U2") (pin "T5") (pinfunction "VSS_T5") (pintype "passive"))
      (node (ref "U2") (pin "T8") (pinfunction "VSS_T8") (pintype "passive"))
      (node (ref "U2") (pin "V1") (pinfunction "VSS_V1") (pintype "passive"))
      (node (ref "U2") (pin "V12") (pinfunction "VSS_V12") (pintype "passive"))
      (node (ref "U2") (pin "V5") (pinfunction "VSS_V5") (pintype "passive"))
      (node (ref "U2") (pin "V8") (pinfunction "VSS_V8") (pintype "passive"))
      (node (ref "U2") (pin "W11") (pinfunction "VSS_W11") (pintype "passive"))
      (node (ref "U2") (pin "W2") (pinfunction "VSS_W2") (pintype "passive"))
      (node (ref "U2") (pin "W4") (pinfunction "VSS_W4") (pintype "passive"))
      (node (ref "U2") (pin "W9") (pinfunction "VSS_W9") (pintype "passive"))
      (node (ref "U2") (pin "Y1") (pinfunction "VSS_Y1") (pintype "passive"))
      (node (ref "U2") (pin "Y12") (pinfunction "VSS_Y12") (pintype "passive"))
      (node (ref "U2") (pin "Y5") (pinfunction "VSS_Y5") (pintype "passive"))
      (node (ref "U2") (pin "Y8") (pinfunction "VSS_Y8") (pintype "passive"))
    )
    (net (code "67") (name "VCC1V8_LPDDR4_B") (class "Default")
      (node (ref "C82") (pin "2") (pinfunction "2_2") (pintype "passive"))
      (node (ref "C83") (pin "2") (pinfunction "2_2") (pintype "passive"))
      (node (ref "C84") (pin "2") (pinfunction "2_2") (pintype "passive"))
      (node (ref "C85") (pin "2") (pinfunction "2_2") (pintype "passive"))
      (node (ref "C86") (pin "2") (pinfunction "2_2") (pintype "passive"))
      (node (ref "C87") (pin "2") (pinfunction "2_2") (pintype "passive"))
      (node (ref "C88") (pin "2") (pinfunction "2_2") (pintype "passive"))
      (node (ref "C89") (pin "2") (pinfunction "2_2") (pintype "passive"))
      (node (ref "C90") (pin "2") (pinfunction "2_2") (pintype "passive"))
      (node (ref "FB2") (pin "2") (pinfunction "2_2") (pintype "passive"))
      (node (ref "U2") (pin "F1") (pinfunction "VDD1_F1") (pintype "passive"))
      (node (ref "U2") (pin "F12") (pinfunction "VDD1_F12") (pintype "passive"))
      (node (ref "U2") (pin "G4") (pinfunction "VDD1_G4") (pintype "passive"))
      (node (ref "U2") (pin "G9") (pinfunction "VDD1_G9") (pintype "passive"))
      (node (ref "U2") (pin "T4") (pinfunction "VDD1_T4") (pintype "passive"))
      (node (ref "U2") (pin "T9") (pinfunction "VDD1_T9") (pintype "passive"))
      (node (ref "U2") (pin "U1") (pinfunction "VDD1_U1") (pintype "passive"))
      (node (ref "U2") (pin "U12") (pinfunction "VDD1_U12") (pintype "passive"))
    )
    (net (code "68") (name "VCC_DDR") (class "Default")
      (node (ref "C46") (pin "2") (pinfunction "2_2") (pintype "passive"))
      (node (ref "C47") (pin "2") (pinfunction "2_2") (pintype "passive"))
      (node (ref "C48") (pin "2") (pinfunction "2_2") (pintype "passive"))
      (node (ref "C49") (pin "2") (pinfunction "2_2") (pintype "passive"))
      (node (ref "C50") (pin "2") (pinfunction "2_2") (pintype "passive"))
      (node (ref "C51") (pin "2") (pinfunction "2_2") (pintype "passive"))
      (node (ref "C52") (pin "2") (pinfunction "2_2") (pintype "passive"))
      (node (ref "C53") (pin "2") (pinfunction "2_2") (pintype "passive"))
      (node (ref "C54") (pin "2") (pinfunction "2_2") (pintype "passive"))
      (node (ref "C64") (pin "2") (pinfunction "2_2") (pintype "passive"))
      (node (ref "C65") (pin "2") (pinfunction "2_2") (pintype "passive"))
      (node (ref "C66") (pin "2") (pinfunction "2_2") (pintype "passive"))
      (node (ref "C67") (pin "2") (pinfunction "2_2") (pintype "passive"))
      (node (ref "C68") (pin "2") (pinfunction "2_2") (pintype "passive"))
      (node (ref "C69") (pin "2") (pinfunction "2_2") (pintype "passive"))
      (node (ref "C70") (pin "2") (pinfunction "2_2") (pintype "passive"))
      (node (ref "C71") (pin "2") (pinfunction "2_2") (pintype "passive"))
      (node (ref "C72") (pin "2") (pinfunction "2_2") (pintype "passive"))
      (node (ref "FB2") (pin "1") (pinfunction "1_1") (pintype "passive"))
      (node (ref "U2") (pin "A4") (pinfunction "VDD2_A4") (pintype "passive"))
      (node (ref "U2") (pin "A9") (pinfunction "VDD2_A9") (pintype "passive"))
      (node (ref "U2") (pin "AB4") (pinfunction "VDD2_AB4") (pintype "passive"))
      (node (ref "U2") (pin "AB9") (pinfunction "VDD2_AB9") (pintype "passive"))
      (node (ref "U2") (pin "F5") (pinfunction "VDD2_F5") (pintype "passive"))
      (node (ref "U2") (pin "F8") (pinfunction "VDD2_F8") (pintype "passive"))
      (node (ref "U2") (pin "H1") (pinfunction "VDD2_H1") (pintype "passive"))
      (node (ref "U2") (pin "H12") (pinfunction "VDD2_H12") (pintype "passive"))
      (node (ref "U2") (pin "H5") (pinfunction "VDD2_H5") (pintype "passive"))
      (node (ref "U2") (pin "H8") (pinfunction "VDD2_H8") (pintype "passive"))
      (node (ref "U2") (pin "K1") (pinfunction "VDD2_K1") (pintype "passive"))
      (node (ref "U2") (pin "K10") (pinfunction "VDD2_K10") (pintype "passive"))
      (node (ref "U2") (pin "K12") (pinfunction "VDD2_K12") (pintype "passive"))
      (node (ref "U2") (pin "K3") (pinfunction "VDD2_K3") (pintype "passive"))
      (node (ref "U2") (pin "N1") (pinfunction "VDD2_N1") (pintype "passive"))
      (node (ref "U2") (pin "N10") (pinfunction "VDD2_N10") (pintype "passive"))
      (node (ref "U2") (pin "N12") (pinfunction "VDD2_N12") (pintype "passive"))
      (node (ref "U2") (pin "N3") (pinfunction "VDD2_N3") (pintype "passive"))
      (node (ref "U2") (pin "R1") (pinfunction "VDD2_R1") (pintype "passive"))
      (node (ref "U2") (pin "R12") (pinfunction "VDD2_R12") (pintype "passive"))
      (node (ref "U2") (pin "R5") (pinfunction "VDD2_R5") (pintype "passive"))
      (node (ref "U2") (pin "R8") (pinfunction "VDD2_R8") (pintype "passive"))
      (node (ref "U2") (pin "U5") (pinfunction "VDD2_U5") (pintype "passive"))
      (node (ref "U2") (pin "U8") (pinfunction "VDD2_U8") (pintype "passive"))
    )
    (net (code "69") (name "VCC_DDRC") (class "Default")
      (node (ref "C55") (pin "2") (pinfunction "2_2") (pintype "passive"))
      (node (ref "C56") (pin "2") (pinfunction "2_2") (pintype "passive"))
      (node (ref "C57") (pin "2") (pinfunction "2_2") (pintype "passive"))
      (node (ref "C58") (pin "2") (pinfunction "2_2") (pintype "passive"))
      (node (ref "C59") (pin "2") (pinfunction "2_2") (pintype "passive"))
      (node (ref "C60") (pin "2") (pinfunction "2_2") (pintype "passive"))
      (node (ref "C61") (pin "2") (pinfunction "2_2") (pintype "passive"))
      (node (ref "C62") (pin "2") (pinfunction "2_2") (pintype "passive"))
      (node (ref "C63") (pin "2") (pinfunction "2_2") (pintype "passive"))
      (node (ref "C73") (pin "2") (pinfunction "2_2") (pintype "passive"))
      (node (ref "C74") (pin "2") (pinfunction "2_2") (pintype "passive"))
      (node (ref "C75") (pin "2") (pinfunction "2_2") (pintype "passive"))
      (node (ref "C76") (pin "2") (pinfunction "2_2") (pintype "passive"))
      (node (ref "C77") (pin "2") (pinfunction "2_2") (pintype "passive"))
      (node (ref "C78") (pin "2") (pinfunction "2_2") (pintype "passive"))
      (node (ref "C79") (pin "2") (pinfunction "2_2") (pintype "passive"))
      (node (ref "C80") (pin "2") (pinfunction "2_2") (pintype "passive"))
      (node (ref "C81") (pin "2") (pinfunction "2_2") (pintype "passive"))
      (node (ref "R5") (pin "2") (pinfunction "2_2") (pintype "passive"))
      (node (ref "R7") (pin "1") (pinfunction "1_1") (pintype "passive"))
      (node (ref "R8") (pin "1") (pinfunction "1_1") (pintype "passive"))
      (node (ref "U2") (pin "AA10") (pinfunction "VDDQ_AA10") (pintype "passive"))
      (node (ref "U2") (pin "AA3") (pinfunction "VDDQ_AA3") (pintype "passive"))
      (node (ref "U2") (pin "AA5") (pinfunction "VDDQ_AA5") (pintype "passive"))
      (node (ref "U2") (pin "AA8") (pinfunction "VDDQ_AA8") (pintype "passive"))
      (node (ref "U2") (pin "B10") (pinfunction "VDDQ_B10") (pintype "passive"))
      (node (ref "U2") (pin "B3") (pinfunction "VDDQ_B3") (pintype "passive"))
      (node (ref "U2") (pin "B5") (pinfunction "VDDQ_B5") (pintype "passive"))
      (node (ref "U2") (pin "B8") (pinfunction "VDDQ_B8") (pintype "passive"))
      (node (ref "U2") (pin "D1") (pinfunction "VDDQ_D1") (pintype "passive"))
      (node (ref "U2") (pin "D12") (pinfunction "VDDQ_D12") (pintype "passive"))
      (node (ref "U2") (pin "D5") (pinfunction "VDDQ_D5") (pintype "passive"))
      (node (ref "U2") (pin "D8") (pinfunction "VDDQ_D8") (pintype "passive"))
      (node (ref "U2") (pin "F10") (pinfunction "VDDQ_F10") (pintype "passive"))
      (node (ref "U2") (pin "F3") (pinfunction "VDDQ_F3") (pintype "passive"))
      (node (ref "U2") (pin "U10") (pinfunction "VDDQ_U10") (pintype "passive"))
      (node (ref "U2") (pin "U3") (pinfunction "VDDQ_U3") (pintype "passive"))
      (node (ref "U2") (pin "W1") (pinfunction "VDDQ_W1") (pintype "passive"))
      (node (ref "U2") (pin "W12") (pinfunction "VDDQ_W12") (pintype "passive"))
      (node (ref "U2") (pin "W5") (pinfunction "VDDQ_W5") (pintype "passive"))
      (node (ref "U2") (pin "W8") (pinfunction "VDDQ_W8") (pintype "passive"))
    )
    (net (code "70") (name "unconnected-(U2B-DNU1-PadA1)") (class "Default")
      (node (ref "U2") (pin "A1") (pinfunction "DNU1_A1") (pintype "passive+no_connect"))
    )
    (net (code "71") (name "unconnected-(U2B-DNU2-PadA2)") (class "Default")
      (node (ref "U2") (pin "A2") (pinfunction "DNU2_A2") (pintype "passive+no_connect"))
    )
    (net (code "72") (name "unconnected-(U2B-DNU3-PadA11)") (class "Default")
      (node (ref "U2") (pin "A11") (pinfunction "DNU3_A11") (pintype "passive+no_connect"))
    )
    (net (code "73") (name "unconnected-(U2B-DNU4-PadA12)") (class "Default")
      (node (ref "U2") (pin "A12") (pinfunction "DNU4_A12") (pintype "passive+no_connect"))
    )
    (net (code "74") (name "unconnected-(U2B-DNU5-PadB1)") (class "Default")
      (node (ref "U2") (pin "B1") (pinfunction "DNU5_B1") (pintype "passive+no_connect"))
    )
    (net (code "75") (name "unconnected-(U2B-DNU6-PadB12)") (class "Default")
      (node (ref "U2") (pin "B12") (pinfunction "DNU6_B12") (pintype "passive+no_connect"))
    )
    (net (code "76") (name "unconnected-(U2B-DNU7-PadAA1)") (class "Default")
      (node (ref "U2") (pin "AA1") (pinfunction "DNU7_AA1") (pintype "passive+no_connect"))
    )
    (net (code "77") (name "unconnected-(U2B-DNU8-PadAA12)") (class "Default")
      (node (ref "U2") (pin "AA12") (pinfunction "DNU8_AA12") (pintype "passive+no_connect"))
    )
    (net (code "78") (name "unconnected-(U2B-DNU9-PadAB1)") (class "Default")
      (node (ref "U2") (pin "AB1") (pinfunction "DNU9_AB1") (pintype "passive+no_connect"))
    )
    (net (code "79") (name "unconnected-(U2B-DNU10-PadAB2)") (class "Default")
      (node (ref "U2") (pin "AB2") (pinfunction "DNU10_AB2") (pintype "passive+no_connect"))
    )
    (net (code "80") (name "unconnected-(U2B-DNU11-PadAB11)") (class "Default")
      (node (ref "U2") (pin "AB11") (pinfunction "DNU11_AB11") (pintype "passive+no_connect"))
    )
    (net (code "81") (name "unconnected-(U2B-DNU12-PadAB12)") (class "Default")
      (node (ref "U2") (pin "AB12") (pinfunction "DNU12_AB12") (pintype "passive+no_connect"))
    )
    (net (code "82") (name "unconnected-(U2B-DNU13-PadK8)") (class "Default")
      (node (ref "U2") (pin "K8") (pinfunction "DNU13_K8") (pintype "passive+no_connect"))
    )
    (net (code "83") (name "unconnected-(U2B-DNU14-PadN5)") (class "Default")
      (node (ref "U2") (pin "N5") (pinfunction "DNU14_N5") (pintype "passive+no_connect"))
    )
    (net (code "84") (name "unconnected-(U2B-DNU15-PadK5)") (class "Default")
      (node (ref "U2") (pin "K5") (pinfunction "DNU15_K5") (pintype "passive+no_connect"))
    )
    (net (code "85") (name "unconnected-(U2B-DNU16-PadG11)") (class "Default")
      (node (ref "U2") (pin "G11") (pinfunction "DNU16_G11") (pintype "passive+no_connect"))
    )
    (net (code "86") (name "unconnected-(U2B-DNU17-PadN8)") (class "Default")
      (node (ref "U2") (pin "N8") (pinfunction "DNU17_N8") (pintype "passive+no_connect"))
    )
  )
)
